# MichelleSheetv2.net
KiCad netlist of a schematic drawn in Altium Designer
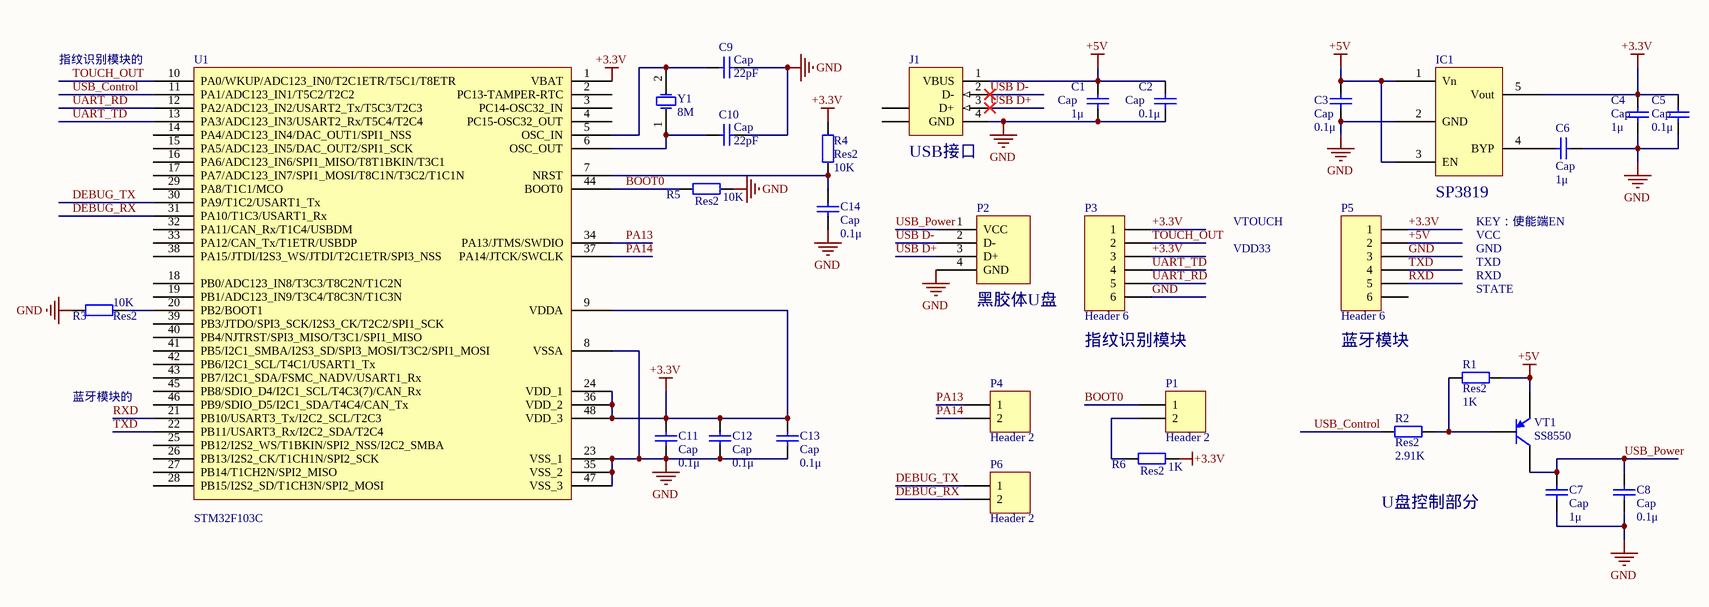
[diagram p0: MichelleSheetv2.SchDoc]

(export (version "E")
  (design (tool "Eeschema 10.0.6"))
  (components
    (comp (ref "C1")
      (value "Cap")
      (footprint "c0603")
      (description "Capacitor")
      (fields (field (name "ALTIUM_VALUE") "1μ") (field (name "PUBLISHER") "Altium Limited"))
      (libsource (lib "Miscellaneous Devices") (part "Cap"))
    )
    (comp (ref "C2")
      (value "Cap")
      (footprint "c0603")
      (description "Capacitor")
      (fields (field (name "ALTIUM_VALUE") "0.1μ") (field (name "PUBLISHER") "Altium Limited"))
      (libsource (lib "Miscellaneous Devices") (part "Cap"))
    )
    (comp (ref "C3")
      (value "Cap")
      (footprint "c0603")
      (description "Capacitor")
      (fields (field (name "ALTIUM_VALUE") "0.1μ") (field (name "PUBLISHER") "Altium Limited"))
      (libsource (lib "Miscellaneous Devices") (part "Cap"))
    )
    (comp (ref "C4")
      (value "Cap")
      (footprint "c0603")
      (description "Capacitor")
      (fields (field (name "ALTIUM_VALUE") "1μ") (field (name "PUBLISHER") "Altium Limited"))
      (libsource (lib "Miscellaneous Devices") (part "Cap"))
    )
    (comp (ref "C5")
      (value "Cap")
      (footprint "c0603")
      (description "Capacitor")
      (fields (field (name "ALTIUM_VALUE") "0.1μ") (field (name "PUBLISHER") "Altium Limited"))
      (libsource (lib "Miscellaneous Devices") (part "Cap"))
    )
    (comp (ref "C6")
      (value "Cap")
      (footprint "c0603")
      (description "Capacitor")
      (fields (field (name "ALTIUM_VALUE") "1μ") (field (name "PUBLISHER") "Altium Limited"))
      (libsource (lib "Miscellaneous Devices") (part "Cap"))
    )
    (comp (ref "C7")
      (value "Cap")
      (footprint "c0603")
      (description "Capacitor")
      (fields (field (name "ALTIUM_VALUE") "1μ") (field (name "PUBLISHER") "Altium Limited"))
      (libsource (lib "Miscellaneous Devices") (part "Cap"))
    )
    (comp (ref "C8")
      (value "Cap")
      (footprint "c0603")
      (description "Capacitor")
      (fields (field (name "ALTIUM_VALUE") "0.1μ") (field (name "PUBLISHER") "Altium Limited"))
      (libsource (lib "Miscellaneous Devices") (part "Cap"))
    )
    (comp (ref "C9")
      (value "Cap")
      (footprint "c0603")
      (description "Capacitor")
      (fields (field (name "ALTIUM_VALUE") "22pF") (field (name "PUBLISHER") "Altium Limited"))
      (libsource (lib "Miscellaneous Devices") (part "Cap"))
    )
    (comp (ref "C10")
      (value "Cap")
      (footprint "c0603")
      (description "Capacitor")
      (fields (field (name "ALTIUM_VALUE") "22pF") (field (name "PUBLISHER") "Altium Limited"))
      (libsource (lib "Miscellaneous Devices") (part "Cap"))
    )
    (comp (ref "C11")
      (value "Cap")
      (footprint "c0603")
      (description "Capacitor")
      (fields (field (name "ALTIUM_VALUE") "0.1μ") (field (name "PUBLISHER") "Altium Limited"))
      (libsource (lib "Miscellaneous Devices") (part "Cap"))
    )
    (comp (ref "C12")
      (value "Cap")
      (footprint "c0603")
      (description "Capacitor")
      (fields (field (name "ALTIUM_VALUE") "0.1μ") (field (name "PUBLISHER") "Altium Limited"))
      (libsource (lib "Miscellaneous Devices") (part "Cap"))
    )
    (comp (ref "C13")
      (value "Cap")
      (footprint "c0603")
      (description "Capacitor")
      (fields (field (name "ALTIUM_VALUE") "0.1μ") (field (name "PUBLISHER") "Altium Limited"))
      (libsource (lib "Miscellaneous Devices") (part "Cap"))
    )
    (comp (ref "C14")
      (value "Cap")
      (footprint "c0603")
      (description "Capacitor")
      (fields (field (name "ALTIUM_VALUE") "0.1μ") (field (name "PUBLISHER") "Altium Limited"))
      (libsource (lib "Miscellaneous Devices") (part "Cap"))
    )
    (comp (ref "IC1") (value "SP3819") (footprint "SOT_23_5") (libsource (lib "SP3819") (part "SP3819")))
    (comp (ref "J1")
      (value "USB接口")
      (footprint "USB_A(M)_SMD")
      (description "USB 1.1, Right Angle, SMT, A Type, Receptacle, 4 Position, Black")
      (fields (field (name "PUBLISHER") "Altium Limited"))
      (libsource (lib "AMP Serial Bus USB") (part "353583-4"))
    )
    (comp (ref "P1")
      (value "Header 2")
      (footprint "HDR1X2")
      (description "Header, 2-Pin")
      (fields (field (name "PUBLISHER") "Altium Limited"))
      (libsource (lib "Miscellaneous Connectors") (part "Header 2"))
    )
    (comp (ref "P2") (value "黑胶体U盘") (footprint "黑胶体U盘") (libsource (lib "SP3819") (part "黑胶体U盘")))
    (comp (ref "P3")
      (value "Header 6")
      (footprint "SH1.0-6P-V")
      (description "接插件")
      (fields (field (name "PUBLISHER") "Altium Limited"))
      (libsource (lib "Fszhang") (part "Header 6"))
    )
    (comp (ref "P4")
      (value "Header 2")
      (footprint "HDR1X2")
      (description "Header, 2-Pin")
      (fields (field (name "PUBLISHER") "Altium Limited"))
      (libsource (lib "Miscellaneous Connectors") (part "Header 2"))
    )
    (comp (ref "P5")
      (value "Header 6")
      (footprint "HDR1X6")
      (description "Header, 6-Pin")
      (fields (field (name "PUBLISHER") "Altium Limited"))
      (libsource (lib "Miscellaneous Connectors") (part "Header 6"))
    )
    (comp (ref "P6")
      (value "Header 2")
      (footprint "HDR1X2")
      (description "Header, 2-Pin")
      (fields (field (name "PUBLISHER") "Altium Limited"))
      (libsource (lib "Miscellaneous Connectors") (part "Header 2"))
    )
    (comp (ref "R1")
      (value "Res2")
      (footprint "r0603")
      (description "Resistor")
      (fields (field (name "ALTIUM_VALUE") "1K") (field (name "PUBLISHER") "Altium Limited"))
      (libsource (lib "") (part "Res2_1"))
    )
    (comp (ref "R2")
      (value "Res2")
      (footprint "r0603")
      (description "Resistor")
      (fields (field (name "ALTIUM_VALUE") "2.91K") (field (name "PUBLISHER") "Altium Limited"))
      (libsource (lib "") (part "Res2_1"))
    )
    (comp (ref "R3")
      (value "Res2")
      (footprint "r0603")
      (description "Resistor")
      (fields (field (name "ALTIUM_VALUE") "10K") (field (name "PUBLISHER") "Altium Limited"))
      (libsource (lib "Miscellaneous Devices") (part "Res2"))
    )
    (comp (ref "R4")
      (value "Res2")
      (footprint "r0603")
      (description "Resistor")
      (fields (field (name "ALTIUM_VALUE") "10K") (field (name "PUBLISHER") "Altium Limited"))
      (libsource (lib "") (part "Res2_2"))
    )
    (comp (ref "R5")
      (value "Res2")
      (footprint "r0603")
      (description "Resistor")
      (fields (field (name "ALTIUM_VALUE") "10K") (field (name "PUBLISHER") "Altium Limited"))
      (libsource (lib "Miscellaneous Devices") (part "Res2"))
    )
    (comp (ref "R6")
      (value "Res2")
      (footprint "r0603")
      (description "Resistor")
      (fields (field (name "ALTIUM_VALUE") "1K") (field (name "PUBLISHER") "Altium Limited"))
      (libsource (lib "Miscellaneous Devices") (part "Res2"))
    )
    (comp (ref "U1")
      (value "STM32F103C")
      (footprint "LQFP_48")
      (description "STM32单片机48引脚")
      (libsource (lib "Fszhang") (part "STM32F103C"))
    )
    (comp (ref "VT1")
      (value "SS8550")
      (footprint "SOT23_3")
      (description "PNP General Purpose Amplifier")
      (fields (field (name "PUBLISHER") "Altium Limited"))
      (libsource (lib "Miscellaneous Devices") (part "2N3906"))
    )
    (comp (ref "Y1")
      (value "8M")
      (footprint "HC-49SMD")
      (description "Crystal Oscillator")
      (fields (field (name "PUBLISHER") "Altium Limited"))
      (libsource (lib "Miscellaneous Devices") (part "XTAL"))
    )
  )
  (nets
    (net (code "1") (name "+3.3V") (class "Default")
      (node (ref "C11") (pin "1") (pinfunction "1_1") (pintype "passive"))
      (node (ref "C12") (pin "1") (pinfunction "1_1") (pintype "passive"))
      (node (ref "C13") (pin "2") (pinfunction "2_2") (pintype "passive"))
      (node (ref "C4") (pin "2") (pinfunction "2_2") (pintype "passive"))
      (node (ref "C5") (pin "2") (pinfunction "2_2") (pintype "passive"))
      (node (ref "IC1") (pin "5") (pinfunction "Vout_5") (pintype "passive"))
      (node (ref "P3") (pin "1") (pinfunction "1_1") (pintype "passive"))
      (node (ref "P3") (pin "3") (pinfunction "3_3") (pintype "passive"))
      (node (ref "P5") (pin "1") (pinfunction "1_1") (pintype "passive"))
      (node (ref "R4") (pin "2") (pinfunction "2_2") (pintype "passive"))
      (node (ref "R6") (pin "1") (pinfunction "1_1") (pintype "passive"))
      (node (ref "U1") (pin "1") (pinfunction "VBAT_1") (pintype "passive"))
      (node (ref "U1") (pin "24") (pinfunction "VDD_1_24") (pintype "passive"))
      (node (ref "U1") (pin "36") (pinfunction "VDD_2_36") (pintype "passive"))
      (node (ref "U1") (pin "48") (pinfunction "VDD_3_48") (pintype "passive"))
      (node (ref "U1") (pin "9") (pinfunction "VDDA_9") (pintype "passive"))
    )
    (net (code "2") (name "+5V") (class "Default")
      (node (ref "C1") (pin "2") (pinfunction "2_2") (pintype "passive"))
      (node (ref "C2") (pin "2") (pinfunction "2_2") (pintype "passive"))
      (node (ref "C3") (pin "2") (pinfunction "2_2") (pintype "passive"))
      (node (ref "IC1") (pin "1") (pinfunction "Vn_1") (pintype "passive"))
      (node (ref "IC1") (pin "3") (pinfunction "EN_3") (pintype "passive"))
      (node (ref "J1") (pin "1") (pinfunction "VBUS_1") (pintype "power_in"))
      (node (ref "P5") (pin "2") (pinfunction "2_2") (pintype "passive"))
      (node (ref "R1") (pin "2") (pinfunction "2_2") (pintype "passive"))
      (node (ref "VT1") (pin "1") (pinfunction "E_1") (pintype "passive"))
    )
    (net (code "3") (name "/BOOT0") (class "Default")
      (node (ref "P1") (pin "1") (pinfunction "1_1") (pintype "passive"))
      (node (ref "R5") (pin "2") (pinfunction "2_2") (pintype "passive"))
      (node (ref "U1") (pin "44") (pinfunction "BOOT0_44") (pintype "passive"))
    )
    (net (code "4") (name "/DEBUG_RX") (class "Default")
      (node (ref "P6") (pin "2") (pinfunction "2_2") (pintype "passive"))
      (node (ref "U1") (pin "31") (pinfunction "PA10/T1C3/USART1_Rx_31") (pintype "passive"))
    )
    (net (code "5") (name "/DEBUG_TX") (class "Default")
      (node (ref "P6") (pin "1") (pinfunction "1_1") (pintype "passive"))
      (node (ref "U1") (pin "30") (pinfunction "PA9/T1C2/USART1_Tx_30") (pintype "passive"))
    )
    (net (code "6") (name "/PA13") (class "Default")
      (node (ref "P4") (pin "1") (pinfunction "1_1") (pintype "passive"))
      (node (ref "U1") (pin "34") (pinfunction "PA13/JTMS/SWDIO_34") (pintype "passive"))
    )
    (net (code "7") (name "/PA14") (class "Default")
      (node (ref "P4") (pin "2") (pinfunction "2_2") (pintype "passive"))
      (node (ref "U1") (pin "37") (pinfunction "PA14/JTCK/SWCLK_37") (pintype "passive"))
    )
    (net (code "8") (name "/RXD") (class "Default")
      (node (ref "P5") (pin "5") (pinfunction "5_5") (pintype "passive"))
      (node (ref "U1") (pin "21") (pinfunction "PB10/USART3_Tx/I2C2_SCL/T2C3_21") (pintype "passive"))
    )
    (net (code "9") (name "/TOUCH_OUT") (class "Default")
      (node (ref "P3") (pin "2") (pinfunction "2_2") (pintype "passive"))
      (node (ref "U1") (pin "10") (pinfunction "PA0/WKUP/ADC123_IN0/T2C1ETR/T5C1/T8ETR_10") (pintype "passive"))
    )
    (net (code "10") (name "/TXD") (class "Default")
      (node (ref "P5") (pin "4") (pinfunction "4_4") (pintype "passive"))
      (node (ref "U1") (pin "22") (pinfunction "PB11/USART3_Rx/I2C2_SDA/T2C4_22") (pintype "passive"))
    )
    (net (code "11") (name "/UART_RD") (class "Default")
      (node (ref "P3") (pin "5") (pinfunction "5_5") (pintype "passive"))
      (node (ref "U1") (pin "12") (pinfunction "PA2/ADC123_IN2/USART2_Tx/T5C3/T2C3_12") (pintype "passive"))
    )
    (net (code "12") (name "/UART_TD") (class "Default")
      (node (ref "P3") (pin "4") (pinfunction "4_4") (pintype "passive"))
      (node (ref "U1") (pin "13") (pinfunction "PA3/ADC123_IN3/USART2_Rx/T5C4/T2C4_13") (pintype "passive"))
    )
    (net (code "13") (name "/USB D+") (class "Default")
      (node (ref "J1") (pin "3") (pinfunction "D+_3") (pintype "input"))
      (node (ref "P2") (pin "3") (pinfunction "D+_3") (pintype "passive"))
    )
    (net (code "14") (name "/USB D-") (class "Default")
      (node (ref "J1") (pin "2") (pinfunction "D-_2") (pintype "input"))
      (node (ref "P2") (pin "2") (pinfunction "D-_2") (pintype "passive"))
    )
    (net (code "15") (name "/USB_Control") (class "Default")
      (node (ref "R2") (pin "1") (pinfunction "1_1") (pintype "passive"))
      (node (ref "U1") (pin "11") (pinfunction "PA1/ADC123_IN1/T5C2/T2C2_11") (pintype "passive"))
    )
    (net (code "16") (name "/USB_Power") (class "Default")
      (node (ref "C7") (pin "2") (pinfunction "2_2") (pintype "passive"))
      (node (ref "C8") (pin "2") (pinfunction "2_2") (pintype "passive"))
      (node (ref "P2") (pin "1") (pinfunction "VCC_1") (pintype "passive"))
      (node (ref "VT1") (pin "3") (pinfunction "C_3") (pintype "passive"))
    )
    (net (code "17") (name "GND") (class "Default")
      (node (ref "C1") (pin "1") (pinfunction "1_1") (pintype "passive"))
      (node (ref "C10") (pin "1") (pinfunction "1_1") (pintype "passive"))
      (node (ref "C11") (pin "2") (pinfunction "2_2") (pintype "passive"))
      (node (ref "C12") (pin "2") (pinfunction "2_2") (pintype "passive"))
      (node (ref "C13") (pin "1") (pinfunction "1_1") (pintype "passive"))
      (node (ref "C14") (pin "2") (pinfunction "2_2") (pintype "passive"))
      (node (ref "C2") (pin "1") (pinfunction "1_1") (pintype "passive"))
      (node (ref "C3") (pin "1") (pinfunction "1_1") (pintype "passive"))
      (node (ref "C4") (pin "1") (pinfunction "1_1") (pintype "passive"))
      (node (ref "C5") (pin "1") (pinfunction "1_1") (pintype "passive"))
      (node (ref "C6") (pin "1") (pinfunction "1_1") (pintype "passive"))
      (node (ref "C7") (pin "1") (pinfunction "1_1") (pintype "passive"))
      (node (ref "C8") (pin "1") (pinfunction "1_1") (pintype "passive"))
      (node (ref "C9") (pin "1") (pinfunction "1_1") (pintype "passive"))
      (node (ref "IC1") (pin "2") (pinfunction "GND_2") (pintype "passive"))
      (node (ref "J1") (pin "4") (pinfunction "GND_4") (pintype "power_in"))
      (node (ref "P2") (pin "4") (pinfunction "GND_4") (pintype "passive"))
      (node (ref "P3") (pin "6") (pinfunction "6_6") (pintype "passive"))
      (node (ref "P5") (pin "3") (pinfunction "3_3") (pintype "passive"))
      (node (ref "R3") (pin "2") (pinfunction "2_2") (pintype "passive"))
      (node (ref "R5") (pin "1") (pinfunction "1_1") (pintype "passive"))
      (node (ref "U1") (pin "23") (pinfunction "VSS_1_23") (pintype "passive"))
      (node (ref "U1") (pin "35") (pinfunction "VSS_2_35") (pintype "passive"))
      (node (ref "U1") (pin "47") (pinfunction "VSS_3_47") (pintype "passive"))
      (node (ref "U1") (pin "8") (pinfunction "VSSA_8") (pintype "passive"))
    )
    (net (code "18") (name "Net-(IC1-BYP)") (class "Default")
      (node (ref "C6") (pin "2") (pinfunction "2_2") (pintype "passive"))
      (node (ref "IC1") (pin "4") (pinfunction "BYP_4") (pintype "passive"))
    )
    (net (code "19") (name "Net-(P1-Pad2)") (class "Default")
      (node (ref "P1") (pin "2") (pinfunction "2_2") (pintype "passive"))
      (node (ref "R6") (pin "2") (pinfunction "2_2") (pintype "passive"))
    )
    (net (code "20") (name "Net-(U1-NRST)") (class "Default")
      (node (ref "C14") (pin "1") (pinfunction "1_1") (pintype "passive"))
      (node (ref "R4") (pin "1") (pinfunction "1_1") (pintype "passive"))
      (node (ref "U1") (pin "7") (pinfunction "NRST_7") (pintype "passive"))
    )
    (net (code "21") (name "Net-(U1-OSC_IN)") (class "Default")
      (node (ref "C9") (pin "2") (pinfunction "2_2") (pintype "passive"))
      (node (ref "U1") (pin "5") (pinfunction "OSC_IN_5") (pintype "passive"))
      (node (ref "Y1") (pin "2") (pinfunction "OSC2_2") (pintype "passive"))
    )
    (net (code "22") (name "Net-(U1-OSC_OUT)") (class "Default")
      (node (ref "C10") (pin "2") (pinfunction "2_2") (pintype "passive"))
      (node (ref "U1") (pin "6") (pinfunction "OSC_OUT_6") (pintype "passive"))
      (node (ref "Y1") (pin "1") (pinfunction "OSC1_1") (pintype "passive"))
    )
    (net (code "23") (name "Net-(U1-PB2{slash}BOOT1)") (class "Default")
      (node (ref "R3") (pin "1") (pinfunction "1_1") (pintype "passive"))
      (node (ref "U1") (pin "20") (pinfunction "PB2/BOOT1_20") (pintype "passive"))
    )
    (net (code "24") (name "Net-(VT1-B)") (class "Default")
      (node (ref "R1") (pin "1") (pinfunction "1_1") (pintype "passive"))
      (node (ref "R2") (pin "2") (pinfunction "2_2") (pintype "passive"))
      (node (ref "VT1") (pin "2") (pinfunction "B_2") (pintype "passive"))
    )
    (net (code "25") (name "unconnected-(J1-SHLD-Pad5)") (class "Default")
      (node (ref "J1") (pin "5") (pinfunction "SHLD_5") (pintype "passive"))
    )
    (net (code "26") (name "unconnected-(J1-SHLD-Pad6)") (class "Default")
      (node (ref "J1") (pin "6") (pinfunction "SHLD_6") (pintype "passive"))
    )
    (net (code "27") (name "unconnected-(P5-Pad6)") (class "Default")
      (node (ref "P5") (pin "6") (pinfunction "6_6") (pintype "passive"))
    )
    (net (code "28") (name "unconnected-(U1-PA4{slash}ADC123_IN4{slash}DAC_OUT1{slash}SPI1_NSS-Pad14)") (class "Default")
      (node (ref "U1") (pin "14") (pinfunction "PA4/ADC123_IN4/DAC_OUT1/SPI1_NSS_14") (pintype "passive"))
    )
    (net (code "29") (name "unconnected-(U1-PA5{slash}ADC123_IN5{slash}DAC_OUT2{slash}SPI1_SCK-Pad15)") (class "Default")
      (node (ref "U1") (pin "15") (pinfunction "PA5/ADC123_IN5/DAC_OUT2/SPI1_SCK_15") (pintype "passive"))
    )
    (net (code "30") (name "unconnected-(U1-PA6{slash}ADC123_IN6{slash}SPI1_MISO{slash}T8T1BKIN{slash}T3C1-Pad16)") (class "Default")
      (node (ref "U1") (pin "16") (pinfunction "PA6/ADC123_IN6/SPI1_MISO/T8T1BKIN/T3C1_16") (pintype "passive"))
    )
    (net (code "31") (name "unconnected-(U1-PA7{slash}ADC123_IN7{slash}SPI1_MOSI{slash}T8C1N{slash}T3C2{slash}T1C1N-Pad17)") (class "Default")
      (node (ref "U1") (pin "17") (pinfunction "PA7/ADC123_IN7/SPI1_MOSI/T8C1N/T3C2/T1C1N_17") (pintype "passive"))
    )
    (net (code "32") (name "unconnected-(U1-PA8{slash}T1C1{slash}MCO-Pad29)") (class "Default")
      (node (ref "U1") (pin "29") (pinfunction "PA8/T1C1/MCO_29") (pintype "passive"))
    )
    (net (code "33") (name "unconnected-(U1-PA11{slash}CAN_Rx{slash}T1C4{slash}USBDM-Pad32)") (class "Default")
      (node (ref "U1") (pin "32") (pinfunction "PA11/CAN_Rx/T1C4/USBDM_32") (pintype "passive"))
    )
    (net (code "34") (name "unconnected-(U1-PA12{slash}CAN_Tx{slash}T1ETR{slash}USBDP-Pad33)") (class "Default")
      (node (ref "U1") (pin "33") (pinfunction "PA12/CAN_Tx/T1ETR/USBDP_33") (pintype "passive"))
    )
    (net (code "35") (name "unconnected-(U1-PA15{slash}JTDI{slash}I2S3_WS{slash}JTDI{slash}T2C1ETR{slash}SPI3_NSS-Pad38)") (class "Default")
      (node (ref "U1") (pin "38") (pinfunction "PA15/JTDI/I2S3_WS/JTDI/T2C1ETR/SPI3_NSS_38") (pintype "passive"))
    )
    (net (code "36") (name "unconnected-(U1-PB0{slash}ADC123_IN8{slash}T3C3{slash}T8C2N{slash}T1C2N-Pad18)") (class "Default")
      (node (ref "U1") (pin "18") (pinfunction "PB0/ADC123_IN8/T3C3/T8C2N/T1C2N_18") (pintype "passive"))
    )
    (net (code "37") (name "unconnected-(U1-PB1{slash}ADC123_IN9{slash}T3C4{slash}T8C3N{slash}T1C3N-Pad19)") (class "Default")
      (node (ref "U1") (pin "19") (pinfunction "PB1/ADC123_IN9/T3C4/T8C3N/T1C3N_19") (pintype "passive"))
    )
    (net (code "38") (name "unconnected-(U1-PB3{slash}JTDO{slash}SPI3_SCK{slash}I2S3_CK{slash}T2C2{slash}SPI1_SCK-Pad39)") (class "Default")
      (node (ref "U1") (pin "39") (pinfunction "PB3/JTDO/SPI3_SCK/I2S3_CK/T2C2/SPI1_SCK_39") (pintype "passive"))
    )
    (net (code "39") (name "unconnected-(U1-PB4{slash}NJTRST{slash}SPI3_MISO{slash}T3C1{slash}SPI1_MISO-Pad40)") (class "Default")
      (node (ref "U1") (pin "40") (pinfunction "PB4/NJTRST/SPI3_MISO/T3C1/SPI1_MISO_40") (pintype "passive"))
    )
    (net (code "40") (name "unconnected-(U1-PB5{slash}I2C1_SMBA{slash}I2S3_SD{slash}SPI3_MOSI{slash}T3C2{slash}SPI1_MOSI-Pad41)") (class "Default")
      (node (ref "U1") (pin "41") (pinfunction "PB5/I2C1_SMBA/I2S3_SD/SPI3_MOSI/T3C2/SPI1_MOSI_41") (pintype "passive"))
    )
    (net (code "41") (name "unconnected-(U1-PB6{slash}I2C1_SCL{slash}T4C1{slash}USART1_Tx-Pad42)") (class "Default")
      (node (ref "U1") (pin "42") (pinfunction "PB6/I2C1_SCL/T4C1/USART1_Tx_42") (pintype "passive"))
    )
    (net (code "42") (name "unconnected-(U1-PB7{slash}I2C1_SDA{slash}FSMC_NADV{slash}USART1_Rx-Pad43)") (class "Default")
      (node (ref "U1") (pin "43") (pinfunction "PB7/I2C1_SDA/FSMC_NADV/USART1_Rx_43") (pintype "passive"))
    )
    (net (code "43") (name "unconnected-(U1-PB8{slash}SDIO_D4{slash}I2C1_SCL{slash}T4C3(7){slash}CAN_Rx-Pad45)") (class "Default")
      (node (ref "U1") (pin "45") (pinfunction "PB8/SDIO_D4/I2C1_SCL/T4C3(7)/CAN_Rx_45") (pintype "passive"))
    )
    (net (code "44") (name "unconnected-(U1-PB9{slash}SDIO_D5{slash}I2C1_SDA{slash}T4C4{slash}CAN_Tx-Pad46)") (class "Default")
      (node (ref "U1") (pin "46") (pinfunction "PB9/SDIO_D5/I2C1_SDA/T4C4/CAN_Tx_46") (pintype "passive"))
    )
    (net (code "45") (name "unconnected-(U1-PB12{slash}I2S2_WS{slash}T1BKIN{slash}SPI2_NSS{slash}I2C2_SMBA-Pad25)") (class "Default")
      (node (ref "U1") (pin "25") (pinfunction "PB12/I2S2_WS/T1BKIN/SPI2_NSS/I2C2_SMBA_25") (pintype "passive"))
    )
    (net (code "46") (name "unconnected-(U1-PB13{slash}I2S2_CK{slash}T1CH1N{slash}SPI2_SCK-Pad26)") (class "Default")
      (node (ref "U1") (pin "26") (pinfunction "PB13/I2S2_CK/T1CH1N/SPI2_SCK_26") (pintype "passive"))
    )
    (net (code "47") (name "unconnected-(U1-PB14{slash}T1CH2N{slash}SPI2_MISO-Pad27)") (class "Default")
      (node (ref "U1") (pin "27") (pinfunction "PB14/T1CH2N/SPI2_MISO_27") (pintype "passive"))
    )
    (net (code "48") (name "unconnected-(U1-PB15{slash}I2S2_SD{slash}T1CH3N{slash}SPI2_MOSI-Pad28)") (class "Default")
      (node (ref "U1") (pin "28") (pinfunction "PB15/I2S2_SD/T1CH3N/SPI2_MOSI_28") (pintype "passive"))
    )
    (net (code "49") (name "unconnected-(U1-PC13-TAMPER-RTC-Pad2)") (class "Default")
      (node (ref "U1") (pin "2") (pinfunction "PC13-TAMPER-RTC_2") (pintype "passive"))
    )
    (net (code "50") (name "unconnected-(U1-PC14-OSC32_IN-Pad3)") (class "Default")
      (node (ref "U1") (pin "3") (pinfunction "PC14-OSC32_IN_3") (pintype "passive"))
    )
    (net (code "51") (name "unconnected-(U1-PC15-OSC32_OUT-Pad4)") (class "Default")
      (node (ref "U1") (pin "4") (pinfunction "PC15-OSC32_OUT_4") (pintype "passive"))
    )
  )
)
